# frets-shift.net
KiCad netlist of a schematic drawn in EAGLE
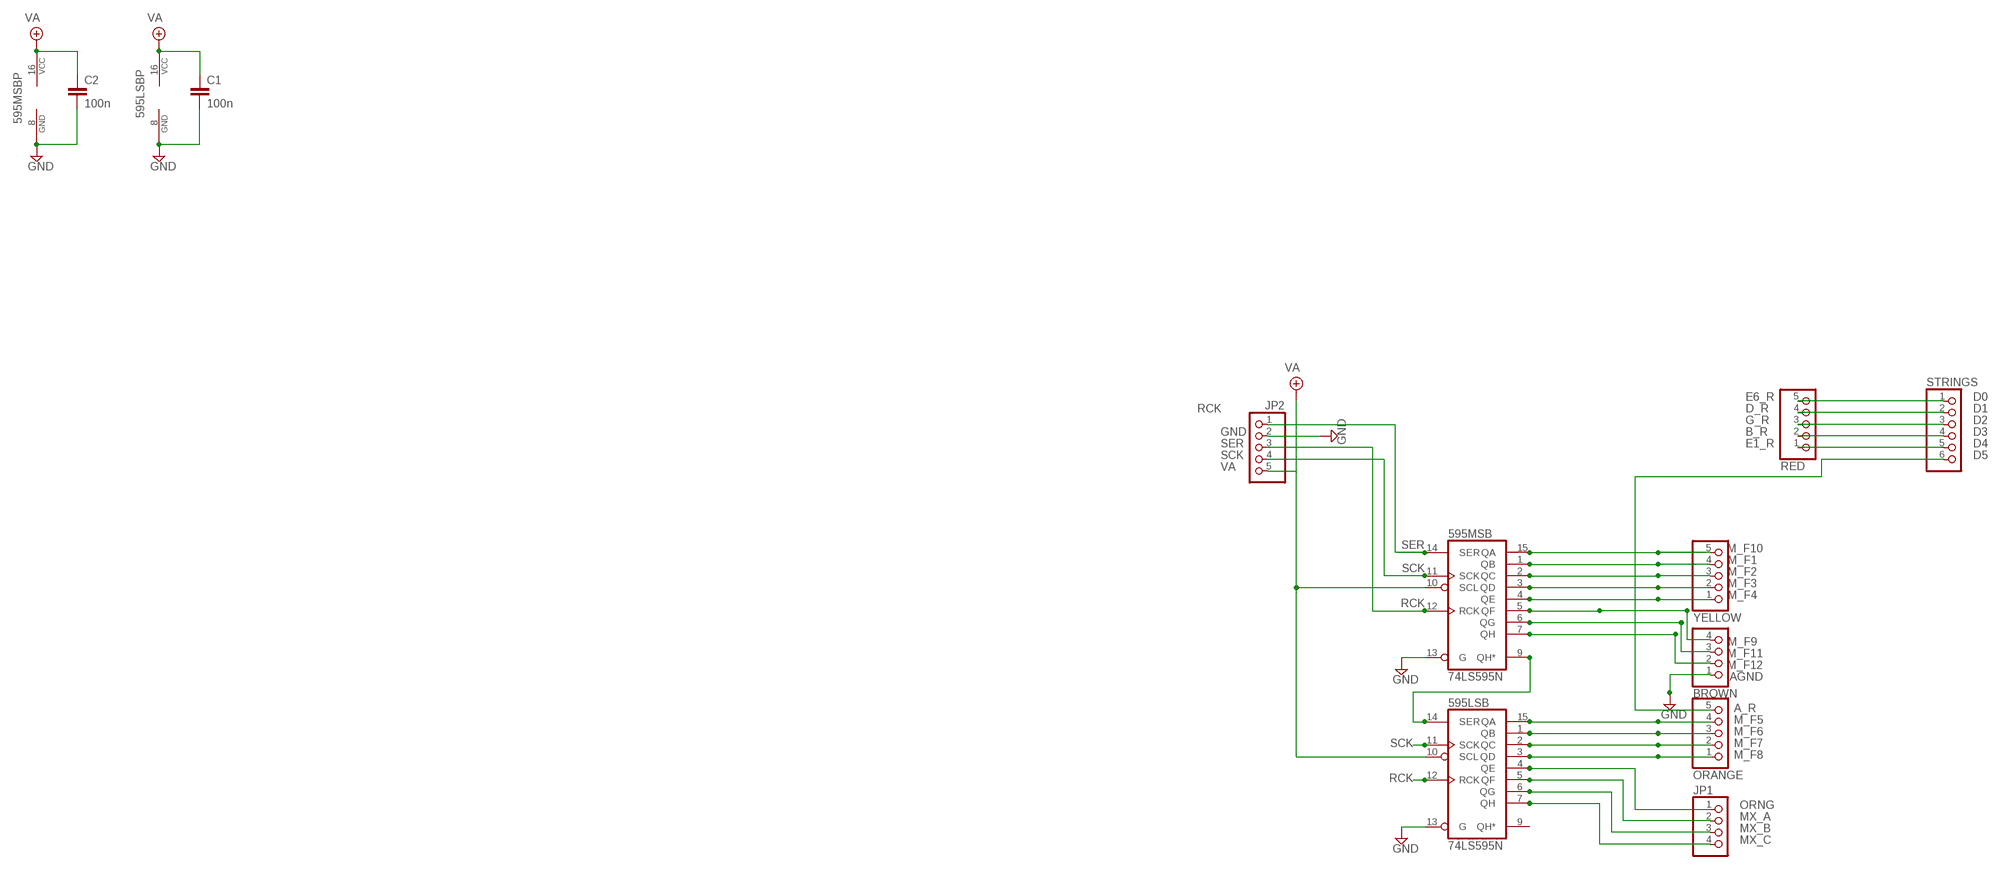
[diagram p0: schematic, sheet 1]

(export (version "E")
  (design (tool "Eeschema 10.0.6"))
  (components
    (comp (ref "595LSB")
      (value "74LS595N")
      (footprint "eagle-import:DIL16")
      (libsource (lib "eagle-import") (part "74595NLS"))
    )
    (comp (ref "595MSB")
      (value "74LS595N")
      (footprint "eagle-import:DIL16")
      (libsource (lib "eagle-import") (part "74595NLS"))
    )
    (comp (ref "BROWN")
      (value "PINHD-1X4")
      (footprint "eagle-import:1X04")
      (libsource (lib "eagle-import") (part "PINHD-1X4"))
    )
    (comp (ref "C1")
      (value "100n")
      (footprint "eagle-import:050X030_050_3")
      (libsource (lib "eagle-import") (part "050X030_050"))
    )
    (comp (ref "C2")
      (value "100n")
      (footprint "eagle-import:050X030_050_3")
      (libsource (lib "eagle-import") (part "050X030_050"))
    )
    (comp (ref "JP1")
      (value "PINHD-1X4")
      (footprint "eagle-import:1X04")
      (libsource (lib "eagle-import") (part "PINHD-1X4"))
    )
    (comp (ref "JP2")
      (value "PINHD-1X5")
      (footprint "eagle-import:1X05")
      (libsource (lib "eagle-import") (part "PINHD-1X5"))
    )
    (comp (ref "ORANGE")
      (value "PINHD-1X5")
      (footprint "eagle-import:1X05")
      (libsource (lib "eagle-import") (part "PINHD-1X5"))
    )
    (comp (ref "RED")
      (value "PINHD-1X5")
      (footprint "eagle-import:1X05")
      (libsource (lib "eagle-import") (part "PINHD-1X5"))
    )
    (comp (ref "STRINGS")
      (value "PINHD-1X6")
      (footprint "eagle-import:1X06")
      (libsource (lib "eagle-import") (part "PINHD-1X6"))
    )
    (comp (ref "YELLOW")
      (value "PINHD-1X5")
      (footprint "eagle-import:1X05")
      (libsource (lib "eagle-import") (part "PINHD-1X5"))
    )
  )
  (nets
    (net (code "1") (name "/D0") (class "Default")
      (node (ref "RED") (pin "5") (pinfunction "5_5") (pintype "passive"))
      (node (ref "STRINGS") (pin "1") (pinfunction "1_1") (pintype "passive"))
    )
    (net (code "2") (name "/D1") (class "Default")
      (node (ref "RED") (pin "4") (pinfunction "4_4") (pintype "passive"))
      (node (ref "STRINGS") (pin "2") (pinfunction "2_2") (pintype "passive"))
    )
    (net (code "3") (name "/D2") (class "Default")
      (node (ref "RED") (pin "3") (pinfunction "3_3") (pintype "passive"))
      (node (ref "STRINGS") (pin "3") (pinfunction "3_3") (pintype "passive"))
    )
    (net (code "4") (name "/D3") (class "Default")
      (node (ref "RED") (pin "2") (pinfunction "2_2") (pintype "passive"))
      (node (ref "STRINGS") (pin "4") (pinfunction "4_4") (pintype "passive"))
    )
    (net (code "5") (name "/D4") (class "Default")
      (node (ref "RED") (pin "1") (pinfunction "1_1") (pintype "passive"))
      (node (ref "STRINGS") (pin "5") (pinfunction "5_5") (pintype "passive"))
    )
    (net (code "6") (name "/D5") (class "Default")
      (node (ref "ORANGE") (pin "5") (pinfunction "5_5") (pintype "passive"))
      (node (ref "STRINGS") (pin "6") (pinfunction "6_6") (pintype "passive"))
    )
    (net (code "7") (name "/MX_A") (class "Default")
      (node (ref "595LSB") (pin "5") (pinfunction "QF_5") (pintype "tri_state"))
      (node (ref "JP1") (pin "2") (pinfunction "2_2") (pintype "passive"))
    )
    (net (code "8") (name "/MX_B") (class "Default")
      (node (ref "595LSB") (pin "6") (pinfunction "QG_6") (pintype "tri_state"))
      (node (ref "JP1") (pin "3") (pinfunction "3_3") (pintype "passive"))
    )
    (net (code "9") (name "/MX_C") (class "Default")
      (node (ref "595LSB") (pin "7") (pinfunction "QH_7") (pintype "tri_state"))
      (node (ref "JP1") (pin "4") (pinfunction "4_4") (pintype "passive"))
    )
    (net (code "10") (name "/ORNG") (class "Default")
      (node (ref "595LSB") (pin "4") (pinfunction "QE_4") (pintype "tri_state"))
      (node (ref "JP1") (pin "1") (pinfunction "1_1") (pintype "passive"))
    )
    (net (code "11") (name "/RCK") (class "Default")
      (node (ref "595LSB") (pin "12") (pinfunction "RCK_12") (pintype "input"))
      (node (ref "595MSB") (pin "12") (pinfunction "RCK_12") (pintype "input"))
      (node (ref "JP2") (pin "3") (pinfunction "3_3") (pintype "passive"))
    )
    (net (code "12") (name "/SCK") (class "Default")
      (node (ref "595LSB") (pin "11") (pinfunction "SCK_11") (pintype "input"))
      (node (ref "595MSB") (pin "11") (pinfunction "SCK_11") (pintype "input"))
      (node (ref "JP2") (pin "4") (pinfunction "4_4") (pintype "passive"))
    )
    (net (code "13") (name "/SER") (class "Default")
      (node (ref "595MSB") (pin "14") (pinfunction "SER_14") (pintype "input"))
      (node (ref "JP2") (pin "1") (pinfunction "1_1") (pintype "passive"))
    )
    (net (code "14") (name "GND") (class "Default")
      (node (ref "595LSB") (pin "13") (pinfunction "G_13") (pintype "input"))
      (node (ref "595LSB") (pin "8") (pinfunction "GND_8") (pintype "power_in"))
      (node (ref "595MSB") (pin "13") (pinfunction "G_13") (pintype "input"))
      (node (ref "595MSB") (pin "8") (pinfunction "GND_8") (pintype "power_in"))
      (node (ref "BROWN") (pin "1") (pinfunction "1_1") (pintype "passive"))
      (node (ref "C1") (pin "2") (pinfunction "2_2") (pintype "passive"))
      (node (ref "C2") (pin "2") (pinfunction "2_2") (pintype "passive"))
      (node (ref "JP2") (pin "2") (pinfunction "2_2") (pintype "passive"))
    )
    (net (code "15") (name "Net-(595LSBA-QA)") (class "Default")
      (node (ref "595LSB") (pin "15") (pinfunction "QA_15") (pintype "tri_state"))
      (node (ref "ORANGE") (pin "4") (pinfunction "4_4") (pintype "passive"))
    )
    (net (code "16") (name "Net-(595LSBA-QB)") (class "Default")
      (node (ref "595LSB") (pin "1") (pinfunction "QB_1") (pintype "tri_state"))
      (node (ref "ORANGE") (pin "3") (pinfunction "3_3") (pintype "passive"))
    )
    (net (code "17") (name "Net-(595LSBA-QC)") (class "Default")
      (node (ref "595LSB") (pin "2") (pinfunction "QC_2") (pintype "tri_state"))
      (node (ref "ORANGE") (pin "2") (pinfunction "2_2") (pintype "passive"))
    )
    (net (code "18") (name "Net-(595LSBA-QD)") (class "Default")
      (node (ref "595LSB") (pin "3") (pinfunction "QD_3") (pintype "tri_state"))
      (node (ref "ORANGE") (pin "1") (pinfunction "1_1") (pintype "passive"))
    )
    (net (code "19") (name "Net-(595LSBA-SER)") (class "Default")
      (node (ref "595LSB") (pin "14") (pinfunction "SER_14") (pintype "input"))
      (node (ref "595MSB") (pin "9") (pinfunction "QH*_9") (pintype "tri_state"))
    )
    (net (code "20") (name "Net-(595MSBA-QA)") (class "Default")
      (node (ref "595MSB") (pin "15") (pinfunction "QA_15") (pintype "tri_state"))
      (node (ref "YELLOW") (pin "5") (pinfunction "5_5") (pintype "passive"))
    )
    (net (code "21") (name "Net-(595MSBA-QB)") (class "Default")
      (node (ref "595MSB") (pin "1") (pinfunction "QB_1") (pintype "tri_state"))
      (node (ref "YELLOW") (pin "4") (pinfunction "4_4") (pintype "passive"))
    )
    (net (code "22") (name "Net-(595MSBA-QC)") (class "Default")
      (node (ref "595MSB") (pin "2") (pinfunction "QC_2") (pintype "tri_state"))
      (node (ref "YELLOW") (pin "3") (pinfunction "3_3") (pintype "passive"))
    )
    (net (code "23") (name "Net-(595MSBA-QD)") (class "Default")
      (node (ref "595MSB") (pin "3") (pinfunction "QD_3") (pintype "tri_state"))
      (node (ref "YELLOW") (pin "2") (pinfunction "2_2") (pintype "passive"))
    )
    (net (code "24") (name "Net-(595MSBA-QE)") (class "Default")
      (node (ref "595MSB") (pin "4") (pinfunction "QE_4") (pintype "tri_state"))
      (node (ref "YELLOW") (pin "1") (pinfunction "1_1") (pintype "passive"))
    )
    (net (code "25") (name "Net-(595MSBA-QF)") (class "Default")
      (node (ref "595MSB") (pin "5") (pinfunction "QF_5") (pintype "tri_state"))
      (node (ref "BROWN") (pin "4") (pinfunction "4_4") (pintype "passive"))
    )
    (net (code "26") (name "Net-(595MSBA-QG)") (class "Default")
      (node (ref "595MSB") (pin "6") (pinfunction "QG_6") (pintype "tri_state"))
      (node (ref "BROWN") (pin "3") (pinfunction "3_3") (pintype "passive"))
    )
    (net (code "27") (name "Net-(595MSBA-QH)") (class "Default")
      (node (ref "595MSB") (pin "7") (pinfunction "QH_7") (pintype "tri_state"))
      (node (ref "BROWN") (pin "2") (pinfunction "2_2") (pintype "passive"))
    )
    (net (code "28") (name "VA") (class "Default")
      (node (ref "595LSB") (pin "10") (pinfunction "SCL_10") (pintype "input"))
      (node (ref "595LSB") (pin "16") (pinfunction "VCC_16") (pintype "power_in"))
      (node (ref "595MSB") (pin "10") (pinfunction "SCL_10") (pintype "input"))
      (node (ref "595MSB") (pin "16") (pinfunction "VCC_16") (pintype "power_in"))
      (node (ref "C1") (pin "1") (pinfunction "1_1") (pintype "passive"))
      (node (ref "C2") (pin "1") (pinfunction "1_1") (pintype "passive"))
      (node (ref "JP2") (pin "5") (pinfunction "5_5") (pintype "passive"))
    )
    (net (code "29") (name "unconnected-(595LSBA-QH*-Pad9)") (class "Default")
      (node (ref "595LSB") (pin "9") (pinfunction "QH*_9") (pintype "tri_state"))
    )
  )
)
